# OR.net
KiCad netlist of a schematic drawn in EAGLE
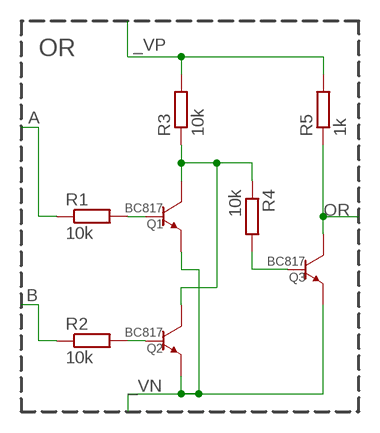
[diagram p0: schematic, sheet 1]

(export (version "E")
  (design (tool "Eeschema 10.0.6"))
  (components
    (comp (ref "Q1")
      (value "BC817")
      (footprint "eagle-import:SOT23")
      (libsource (lib "eagle-import") (part "TRANSISTOR-NPN-GENERIC-SOT23-BECDEFAULT"))
    )
    (comp (ref "Q2")
      (value "BC817")
      (footprint "eagle-import:SOT23")
      (libsource (lib "eagle-import") (part "TRANSISTOR-NPN-GENERIC-SOT23-BECDEFAULT"))
    )
    (comp (ref "Q3")
      (value "BC817")
      (footprint "eagle-import:SOT23")
      (libsource (lib "eagle-import") (part "TRANSISTOR-NPN-GENERIC-SOT23-BECDEFAULT"))
    )
    (comp (ref "R1")
      (value "10k")
      (footprint "eagle-import:R0603")
      (libsource (lib "eagle-import") (part "R-EU_R0603"))
    )
    (comp (ref "R2")
      (value "10k")
      (footprint "eagle-import:R0603")
      (libsource (lib "eagle-import") (part "R-EU_R0603"))
    )
    (comp (ref "R3")
      (value "10k")
      (footprint "eagle-import:R0603")
      (libsource (lib "eagle-import") (part "R-EU_R0603"))
    )
    (comp (ref "R4")
      (value "10k")
      (footprint "eagle-import:R0603")
      (libsource (lib "eagle-import") (part "R-EU_R0603"))
    )
    (comp (ref "R5")
      (value "1k")
      (footprint "eagle-import:R0603")
      (libsource (lib "eagle-import") (part "R-EU_R0603"))
    )
  )
  (nets
    (net (code "1") (name "/A") (class "Default")
      (node (ref "R1") (pin "1") (pinfunction "1_1") (pintype "passive"))
    )
    (net (code "2") (name "/B") (class "Default")
      (node (ref "R2") (pin "1") (pinfunction "1_1") (pintype "passive"))
    )
    (net (code "3") (name "/OR") (class "Default")
      (node (ref "Q3") (pin "P$3") (pinfunction "COLLECTOR_P$3") (pintype "bidirectional"))
      (node (ref "R5") (pin "1") (pinfunction "1_1") (pintype "passive"))
    )
    (net (code "4") (name "/_VN") (class "Default")
      (node (ref "Q1") (pin "P$2") (pinfunction "EMITTER_P$2") (pintype "bidirectional"))
      (node (ref "Q2") (pin "P$2") (pinfunction "EMITTER_P$2") (pintype "bidirectional"))
      (node (ref "Q3") (pin "P$2") (pinfunction "EMITTER_P$2") (pintype "bidirectional"))
    )
    (net (code "5") (name "/_VP") (class "Default")
      (node (ref "R3") (pin "2") (pinfunction "2_2") (pintype "passive"))
      (node (ref "R5") (pin "2") (pinfunction "2_2") (pintype "passive"))
    )
    (net (code "6") (name "Net-(Q1-BASE)") (class "Default")
      (node (ref "Q1") (pin "P$1") (pinfunction "BASE_P$1") (pintype "bidirectional"))
      (node (ref "R1") (pin "2") (pinfunction "2_2") (pintype "passive"))
    )
    (net (code "7") (name "Net-(Q1-COLLECTOR)") (class "Default")
      (node (ref "Q1") (pin "P$3") (pinfunction "COLLECTOR_P$3") (pintype "bidirectional"))
      (node (ref "Q2") (pin "P$3") (pinfunction "COLLECTOR_P$3") (pintype "bidirectional"))
      (node (ref "R3") (pin "1") (pinfunction "1_1") (pintype "passive"))
      (node (ref "R4") (pin "1") (pinfunction "1_1") (pintype "passive"))
    )
    (net (code "8") (name "Net-(Q2-BASE)") (class "Default")
      (node (ref "Q2") (pin "P$1") (pinfunction "BASE_P$1") (pintype "bidirectional"))
      (node (ref "R2") (pin "2") (pinfunction "2_2") (pintype "passive"))
    )
    (net (code "9") (name "Net-(Q3-BASE)") (class "Default")
      (node (ref "Q3") (pin "P$1") (pinfunction "BASE_P$1") (pintype "bidirectional"))
      (node (ref "R4") (pin "2") (pinfunction "2_2") (pintype "passive"))
    )
  )
)
